# Daughter_Board.net
KiCad netlist of a schematic drawn in EAGLE
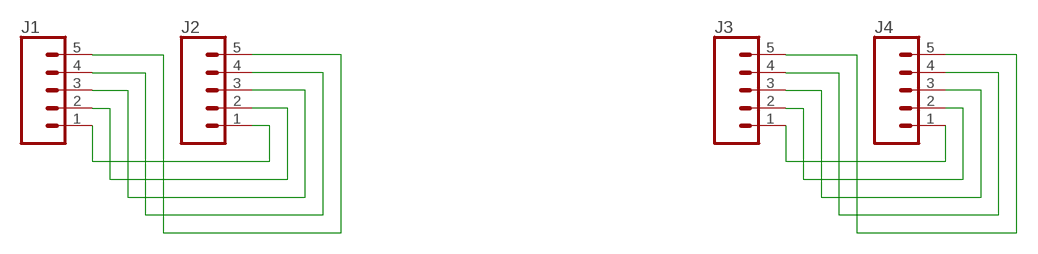
[diagram p0: schematic, sheet 1]

(export (version "E")
  (design (tool "Eeschema 10.0.6"))
  (components
    (comp (ref "J1")
      (value "CONN_05")
      (footprint "eagle-import:1X05")
      (libsource (lib "eagle-import") (part "CONN_05"))
    )
    (comp (ref "J2")
      (value "CONN_05")
      (footprint "eagle-import:1X05")
      (libsource (lib "eagle-import") (part "CONN_05"))
    )
    (comp (ref "J3")
      (value "CONN_05")
      (footprint "eagle-import:1X05")
      (libsource (lib "eagle-import") (part "CONN_05"))
    )
    (comp (ref "J4")
      (value "CONN_05")
      (footprint "eagle-import:1X05")
      (libsource (lib "eagle-import") (part "CONN_05"))
    )
  )
  (nets
    (net (code "1") (name "Net-(J1-Pad1)") (class "Default")
      (node (ref "J1") (pin "1") (pinfunction "1_1") (pintype "passive"))
      (node (ref "J2") (pin "1") (pinfunction "1_1") (pintype "passive"))
    )
    (net (code "2") (name "Net-(J1-Pad2)") (class "Default")
      (node (ref "J1") (pin "2") (pinfunction "2_2") (pintype "passive"))
      (node (ref "J2") (pin "2") (pinfunction "2_2") (pintype "passive"))
    )
    (net (code "3") (name "Net-(J1-Pad3)") (class "Default")
      (node (ref "J1") (pin "3") (pinfunction "3_3") (pintype "passive"))
      (node (ref "J2") (pin "3") (pinfunction "3_3") (pintype "passive"))
    )
    (net (code "4") (name "Net-(J1-Pad4)") (class "Default")
      (node (ref "J1") (pin "4") (pinfunction "4_4") (pintype "passive"))
      (node (ref "J2") (pin "4") (pinfunction "4_4") (pintype "passive"))
    )
    (net (code "5") (name "Net-(J1-Pad5)") (class "Default")
      (node (ref "J1") (pin "5") (pinfunction "5_5") (pintype "passive"))
      (node (ref "J2") (pin "5") (pinfunction "5_5") (pintype "passive"))
    )
    (net (code "6") (name "Net-(J3-Pad1)") (class "Default")
      (node (ref "J3") (pin "1") (pinfunction "1_1") (pintype "passive"))
      (node (ref "J4") (pin "1") (pinfunction "1_1") (pintype "passive"))
    )
    (net (code "7") (name "Net-(J3-Pad2)") (class "Default")
      (node (ref "J3") (pin "2") (pinfunction "2_2") (pintype "passive"))
      (node (ref "J4") (pin "2") (pinfunction "2_2") (pintype "passive"))
    )
    (net (code "8") (name "Net-(J3-Pad3)") (class "Default")
      (node (ref "J3") (pin "3") (pinfunction "3_3") (pintype "passive"))
      (node (ref "J4") (pin "3") (pinfunction "3_3") (pintype "passive"))
    )
    (net (code "9") (name "Net-(J3-Pad4)") (class "Default")
      (node (ref "J3") (pin "4") (pinfunction "4_4") (pintype "passive"))
      (node (ref "J4") (pin "4") (pinfunction "4_4") (pintype "passive"))
    )
    (net (code "10") (name "Net-(J3-Pad5)") (class "Default")
      (node (ref "J3") (pin "5") (pinfunction "5_5") (pintype "passive"))
      (node (ref "J4") (pin "5") (pinfunction "5_5") (pintype "passive"))
    )
  )
)
